# Esquem_tico.net
KiCad netlist of a schematic drawn in EAGLE
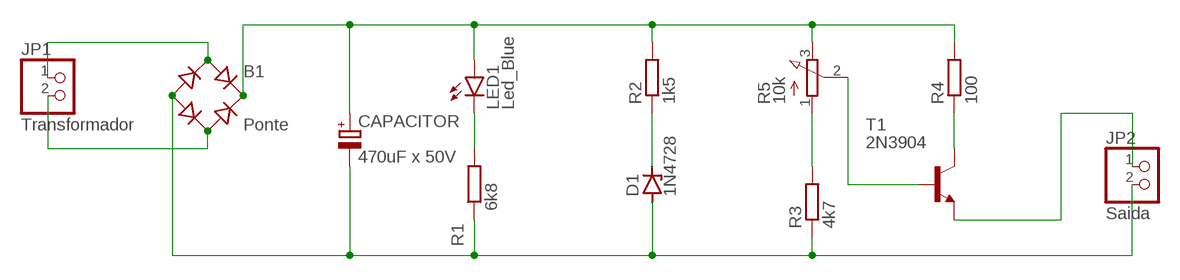
[diagram p0: schematic, sheet 1]

(export (version "E")
  (design (tool "Eeschema 10.0.6"))
  (components
    (comp (ref "B1")
      (value "Ponte")
      (footprint "eagle-import:RB1A")
      (libsource (lib "eagle-import") (part "RB1A"))
    )
    (comp (ref "CAPACITOR")
      (value "470uF x 50V")
      (footprint "eagle-import:E5-10,5")
      (libsource (lib "eagle-import") (part "CPOL-EUE5-10.5"))
    )
    (comp (ref "D1")
      (value "1N4728")
      (footprint "eagle-import:DO41Z10")
      (libsource (lib "eagle-import") (part "1N4728"))
    )
    (comp (ref "JP1")
      (value "Transformador")
      (footprint "eagle-import:1X02")
      (libsource (lib "eagle-import") (part "PINHD-1X2"))
    )
    (comp (ref "JP2")
      (value "Saida")
      (footprint "eagle-import:1X02")
      (libsource (lib "eagle-import") (part "PINHD-1X2"))
    )
    (comp (ref "LED1")
      (value "Led_Blue")
      (footprint "eagle-import:LED5MM")
      (libsource (lib "eagle-import") (part "LED5MM"))
    )
    (comp (ref "R1")
      (value "6k8")
      (footprint "eagle-import:0204_7")
      (libsource (lib "eagle-import") (part "R-EU_0204/7"))
    )
    (comp (ref "R2")
      (value "1k5")
      (footprint "eagle-import:0204_7")
      (libsource (lib "eagle-import") (part "R-EU_0204/7"))
    )
    (comp (ref "R3")
      (value "4k7")
      (footprint "eagle-import:0204_7")
      (libsource (lib "eagle-import") (part "R-EU_0204/7"))
    )
    (comp (ref "R4")
      (value "100")
      (footprint "eagle-import:0207_10")
      (libsource (lib "eagle-import") (part "R-EU_0207/10"))
    )
    (comp (ref "R5")
      (value "10k")
      (footprint "eagle-import:3RP_1610N")
      (libsource (lib "eagle-import") (part "3RP/1610N"))
    )
    (comp (ref "T1")
      (value "2N3904")
      (footprint "eagle-import:TO92")
      (libsource (lib "eagle-import") (part "2N3904"))
    )
  )
  (nets
    (net (code "1") (name "Net-(B1-Pad-)") (class "Default")
      (node (ref "B1") (pin "-") (pinfunction "-_-") (pintype "passive"))
      (node (ref "CAPACITOR") (pin "-") (pinfunction "-_-") (pintype "passive"))
      (node (ref "D1") (pin "A") (pinfunction "A_A") (pintype "passive"))
      (node (ref "JP2") (pin "2") (pinfunction "2_2") (pintype "passive"))
      (node (ref "R1") (pin "1") (pinfunction "1_1") (pintype "passive"))
      (node (ref "R3") (pin "1") (pinfunction "1_1") (pintype "passive"))
    )
    (net (code "2") (name "Net-(B1-PadAC1)") (class "Default")
      (node (ref "B1") (pin "AC1") (pinfunction "AC1_AC1") (pintype "passive"))
      (node (ref "JP1") (pin "1") (pinfunction "1_1") (pintype "passive"))
    )
    (net (code "3") (name "Net-(B1-PadAC2)") (class "Default")
      (node (ref "B1") (pin "AC2") (pinfunction "AC2_AC2") (pintype "passive"))
      (node (ref "JP1") (pin "2") (pinfunction "2_2") (pintype "passive"))
    )
    (net (code "4") (name "Net-(D1-PadC)") (class "Default")
      (node (ref "D1") (pin "C") (pinfunction "C_C") (pintype "passive"))
      (node (ref "R2") (pin "1") (pinfunction "1_1") (pintype "passive"))
    )
    (net (code "5") (name "Net-(LED1-C)") (class "Default")
      (node (ref "LED1") (pin "K") (pinfunction "C_K") (pintype "passive"))
      (node (ref "R1") (pin "2") (pinfunction "2_2") (pintype "passive"))
    )
    (net (code "6") (name "Net-(R5-A)") (class "Default")
      (node (ref "R3") (pin "2") (pinfunction "2_2") (pintype "passive"))
      (node (ref "R5") (pin "1") (pinfunction "A_1") (pintype "passive"))
    )
    (net (code "7") (name "Net-(R5-E)") (class "Default")
      (node (ref "B1") (pin "+") (pinfunction "+_+") (pintype "passive"))
      (node (ref "CAPACITOR") (pin "+") (pinfunction "+_+") (pintype "passive"))
      (node (ref "LED1") (pin "A") (pinfunction "A_A") (pintype "passive"))
      (node (ref "R2") (pin "2") (pinfunction "2_2") (pintype "passive"))
      (node (ref "R4") (pin "2") (pinfunction "2_2") (pintype "passive"))
      (node (ref "R5") (pin "3") (pinfunction "E_3") (pintype "passive"))
    )
    (net (code "8") (name "Net-(R5-S)") (class "Default")
      (node (ref "R5") (pin "2") (pinfunction "S_2") (pintype "passive"))
      (node (ref "T1") (pin "2") (pinfunction "B_2") (pintype "passive"))
    )
    (net (code "9") (name "Net-(T1-C)") (class "Default")
      (node (ref "R4") (pin "1") (pinfunction "1_1") (pintype "passive"))
      (node (ref "T1") (pin "1") (pinfunction "C_1") (pintype "passive"))
    )
    (net (code "10") (name "Net-(T1-E)") (class "Default")
      (node (ref "JP2") (pin "1") (pinfunction "1_1") (pintype "passive"))
      (node (ref "T1") (pin "3") (pinfunction "E_3") (pintype "passive"))
    )
  )
)
